# driver_module.net
KiCad netlist of a schematic drawn in EAGLE
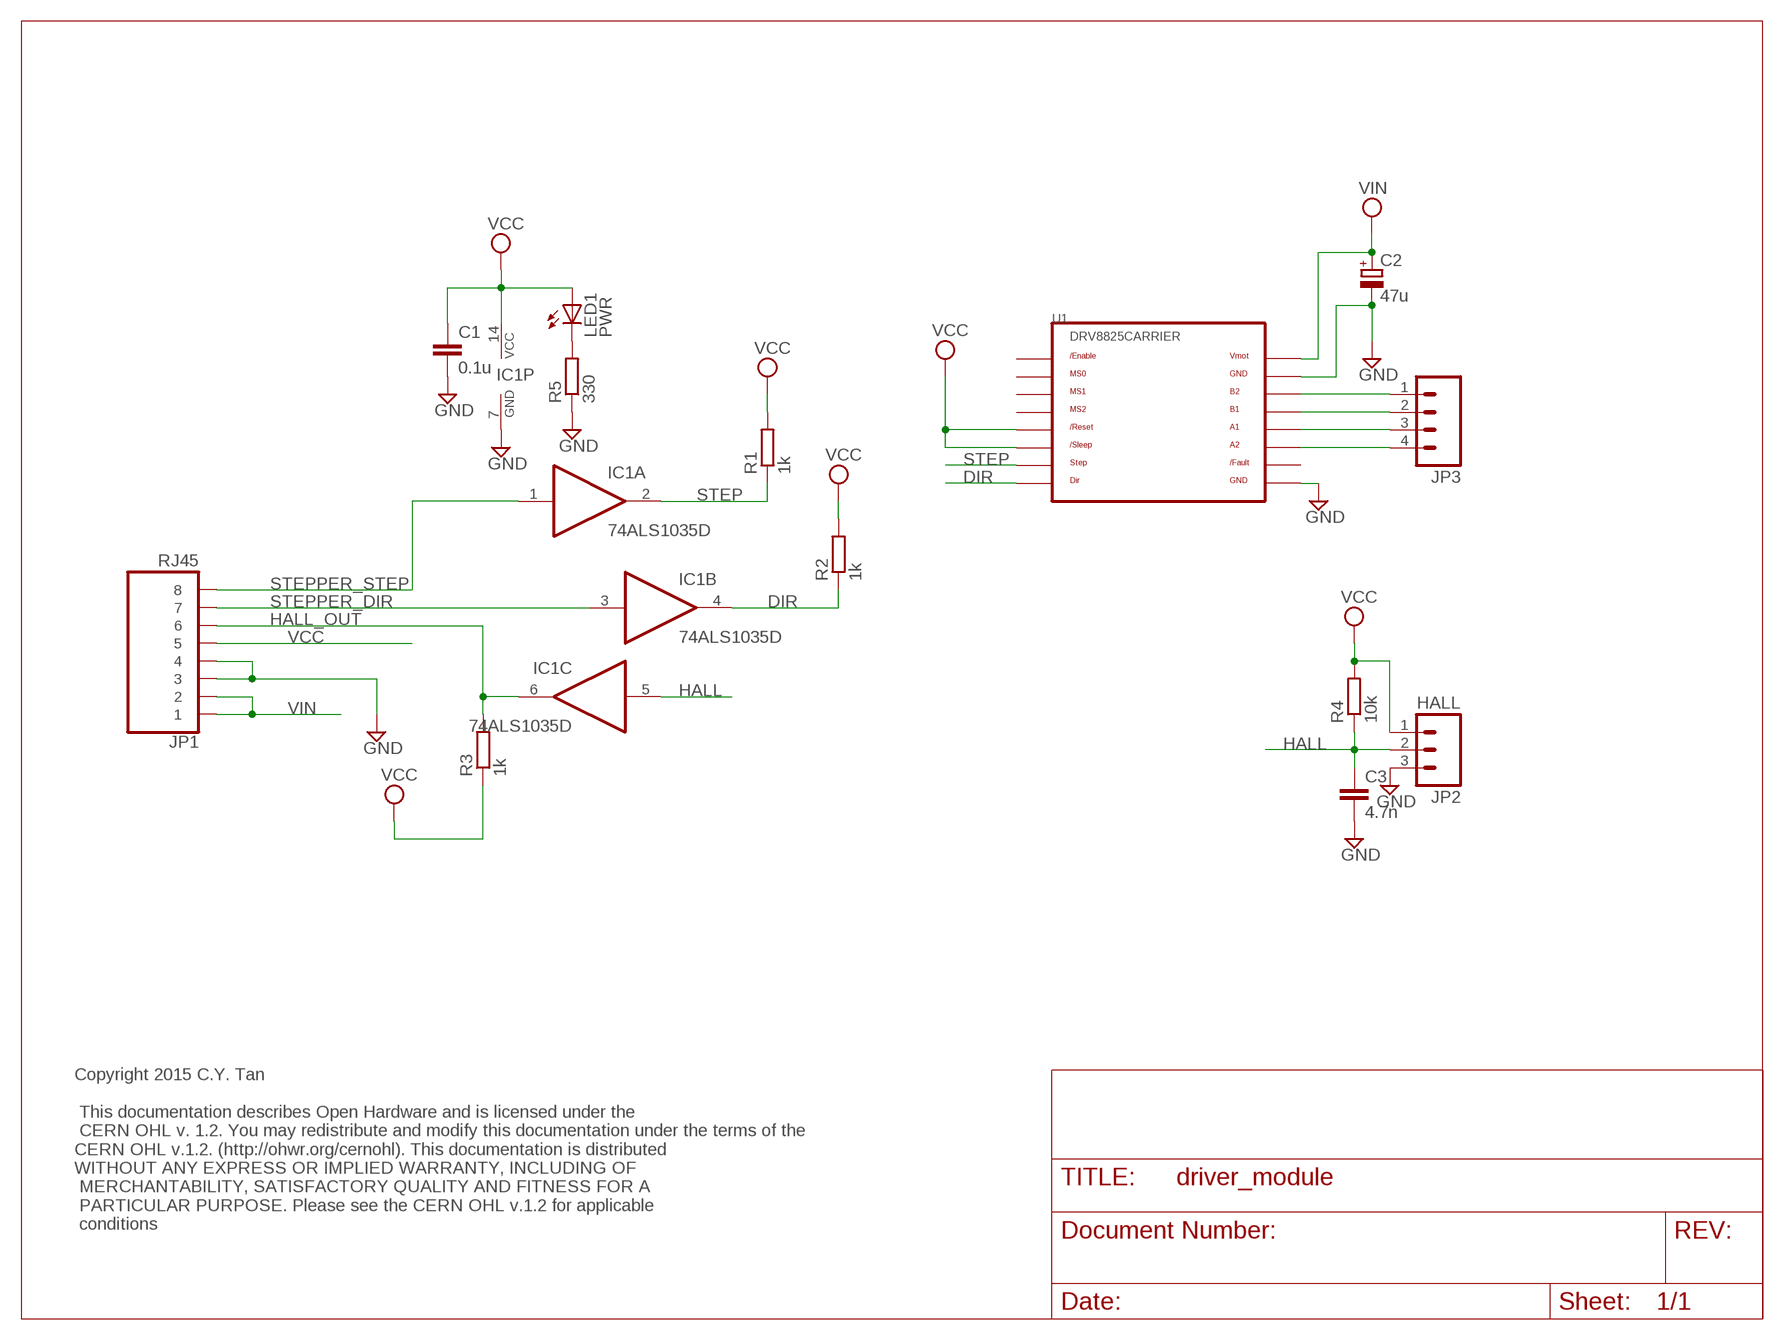
[diagram p0: schematic, sheet 1]

(export (version "E")
  (design (tool "Eeschema 10.0.6"))
  (components
    (comp (ref "C1")
      (value "0.1u")
      (footprint "eagle-import:C1206")
      (libsource (lib "eagle-import") (part "C-EUC1206"))
    )
    (comp (ref "C2")
      (value "47u")
      (footprint "eagle-import:E2,5-6")
      (libsource (lib "eagle-import") (part "CPOL-EUE2.5-6"))
    )
    (comp (ref "C3")
      (value "4.7n")
      (footprint "eagle-import:C1206")
      (libsource (lib "eagle-import") (part "C-EUC1206"))
    )
    (comp (ref "IC1")
      (value "74ALS1035D")
      (footprint "eagle-import:SO14")
      (libsource (lib "eagle-import") (part "74ALS1035D"))
    )
    (comp (ref "JP1")
      (value "RJ45")
      (footprint "eagle-import:RJ45-8")
      (libsource (lib "eagle-import") (part "RJ45-8PTH"))
    )
    (comp (ref "JP2")
      (value "HALL")
      (footprint "eagle-import:1X03")
      (libsource (lib "eagle-import") (part "M03PTH"))
    )
    (comp (ref "JP3")
      (value "M04PTH")
      (footprint "eagle-import:1X04")
      (libsource (lib "eagle-import") (part "M04PTH"))
    )
    (comp (ref "LED1")
      (value "PWR")
      (footprint "eagle-import:CHIPLED_1206")
      (libsource (lib "eagle-import") (part "LEDCHIPLED_1206"))
    )
    (comp (ref "R1")
      (value "1k")
      (footprint "eagle-import:M0805")
      (libsource (lib "eagle-import") (part "R-EU_M0805"))
    )
    (comp (ref "R2")
      (value "1k")
      (footprint "eagle-import:M0805")
      (libsource (lib "eagle-import") (part "R-EU_M0805"))
    )
    (comp (ref "R3")
      (value "1k")
      (footprint "eagle-import:M0805")
      (libsource (lib "eagle-import") (part "R-EU_M0805"))
    )
    (comp (ref "R4")
      (value "10k")
      (footprint "eagle-import:M0805")
      (libsource (lib "eagle-import") (part "R-EU_M0805"))
    )
    (comp (ref "R5")
      (value "330")
      (footprint "eagle-import:M0805")
      (libsource (lib "eagle-import") (part "R-EU_M0805"))
    )
    (comp (ref "U1")
      (value "DRV8825CARRIER")
      (footprint "eagle-import:DRV8825CARRIER")
      (libsource (lib "eagle-import") (part "DRV8825CARRIER"))
    )
  )
  (nets
    (net (code "1") (name "/DIR") (class "Default")
      (node (ref "IC1") (pin "4") (pinfunction "O_4") (pintype "open_collector"))
      (node (ref "R2") (pin "1") (pinfunction "1_1") (pintype "passive"))
      (node (ref "U1") (pin "DIR") (pinfunction "DIR_DIR") (pintype "input"))
    )
    (net (code "2") (name "/HALL") (class "Default")
      (node (ref "C3") (pin "1") (pinfunction "1_1") (pintype "passive"))
      (node (ref "IC1") (pin "5") (pinfunction "I_5") (pintype "input"))
      (node (ref "JP2") (pin "2") (pinfunction "2_2") (pintype "passive"))
      (node (ref "R4") (pin "1") (pinfunction "1_1") (pintype "passive"))
    )
    (net (code "3") (name "/HALL_OUT") (class "Default")
      (node (ref "IC1") (pin "6") (pinfunction "O_6") (pintype "open_collector"))
      (node (ref "JP1") (pin "6") (pinfunction "6_6") (pintype "bidirectional"))
      (node (ref "R3") (pin "2") (pinfunction "2_2") (pintype "passive"))
    )
    (net (code "4") (name "/STEP") (class "Default")
      (node (ref "IC1") (pin "2") (pinfunction "O_2") (pintype "open_collector"))
      (node (ref "R1") (pin "1") (pinfunction "1_1") (pintype "passive"))
      (node (ref "U1") (pin "STEP") (pinfunction "STEP_STEP") (pintype "input"))
    )
    (net (code "5") (name "/STEPPER_DIR") (class "Default")
      (node (ref "IC1") (pin "3") (pinfunction "I_3") (pintype "input"))
      (node (ref "JP1") (pin "7") (pinfunction "7_7") (pintype "bidirectional"))
    )
    (net (code "6") (name "/STEPPER_STEP") (class "Default")
      (node (ref "IC1") (pin "1") (pinfunction "I_1") (pintype "input"))
      (node (ref "JP1") (pin "8") (pinfunction "8_8") (pintype "bidirectional"))
    )
    (net (code "7") (name "/{slash}FAULT") (class "Default")
      (node (ref "U1") (pin "/FAULT") (pinfunction "/FAULT_/FAULT") (pintype "power_in"))
    )
    (net (code "8") (name "GND") (class "Default")
      (node (ref "C1") (pin "2") (pinfunction "2_2") (pintype "passive"))
      (node (ref "C2") (pin "-") (pinfunction "-_-") (pintype "passive"))
      (node (ref "C3") (pin "2") (pinfunction "2_2") (pintype "passive"))
      (node (ref "IC1") (pin "7") (pinfunction "GND_7") (pintype "power_in"))
      (node (ref "JP1") (pin "3") (pinfunction "3_3") (pintype "bidirectional"))
      (node (ref "JP1") (pin "4") (pinfunction "4_4") (pintype "bidirectional"))
      (node (ref "JP2") (pin "3") (pinfunction "3_3") (pintype "passive"))
      (node (ref "R5") (pin "1") (pinfunction "1_1") (pintype "passive"))
      (node (ref "U1") (pin "GND@0") (pinfunction "GND_GND@0") (pintype "power_in"))
      (node (ref "U1") (pin "GND@1") (pinfunction "GND_GND@1") (pintype "power_in"))
    )
    (net (code "9") (name "Net-(JP3-Pad1)") (class "Default")
      (node (ref "JP3") (pin "1") (pinfunction "1_1") (pintype "passive"))
      (node (ref "U1") (pin "B2") (pinfunction "B2_B2") (pintype "output"))
    )
    (net (code "10") (name "Net-(JP3-Pad2)") (class "Default")
      (node (ref "JP3") (pin "2") (pinfunction "2_2") (pintype "passive"))
      (node (ref "U1") (pin "B1") (pinfunction "B1_B1") (pintype "output"))
    )
    (net (code "11") (name "Net-(JP3-Pad3)") (class "Default")
      (node (ref "JP3") (pin "3") (pinfunction "3_3") (pintype "passive"))
      (node (ref "U1") (pin "A1") (pinfunction "A1_A1") (pintype "output"))
    )
    (net (code "12") (name "Net-(JP3-Pad4)") (class "Default")
      (node (ref "JP3") (pin "4") (pinfunction "4_4") (pintype "passive"))
      (node (ref "U1") (pin "A2") (pinfunction "A2_A2") (pintype "output"))
    )
    (net (code "13") (name "Net-(LED1-PadC)") (class "Default")
      (node (ref "LED1") (pin "C") (pinfunction "C_C") (pintype "passive"))
      (node (ref "R5") (pin "2") (pinfunction "2_2") (pintype "passive"))
    )
    (net (code "14") (name "VCC") (class "Default")
      (node (ref "C1") (pin "1") (pinfunction "1_1") (pintype "passive"))
      (node (ref "IC1") (pin "14") (pinfunction "VCC_14") (pintype "power_in"))
      (node (ref "JP1") (pin "5") (pinfunction "5_5") (pintype "bidirectional"))
      (node (ref "JP2") (pin "1") (pinfunction "1_1") (pintype "passive"))
      (node (ref "LED1") (pin "A") (pinfunction "A_A") (pintype "passive"))
      (node (ref "R1") (pin "2") (pinfunction "2_2") (pintype "passive"))
      (node (ref "R2") (pin "2") (pinfunction "2_2") (pintype "passive"))
      (node (ref "R3") (pin "1") (pinfunction "1_1") (pintype "passive"))
      (node (ref "R4") (pin "2") (pinfunction "2_2") (pintype "passive"))
      (node (ref "U1") (pin "/RESET") (pinfunction "/RESET_/RESET") (pintype "input"))
      (node (ref "U1") (pin "/SLEEP") (pinfunction "/SLEEP_/SLEEP") (pintype "input"))
    )
    (net (code "15") (name "VIN") (class "Default")
      (node (ref "C2") (pin "+") (pinfunction "+_+") (pintype "passive"))
      (node (ref "JP1") (pin "1") (pinfunction "1_1") (pintype "bidirectional"))
      (node (ref "JP1") (pin "2") (pinfunction "2_2") (pintype "bidirectional"))
      (node (ref "U1") (pin "VMOT") (pinfunction "VMOT_VMOT") (pintype "power_in"))
    )
    (net (code "16") (name "unconnected-(U1-MS0-PadM0)") (class "Default")
      (node (ref "U1") (pin "M0") (pinfunction "MS0_M0") (pintype "input"))
    )
    (net (code "17") (name "unconnected-(U1-MS1-PadM1)") (class "Default")
      (node (ref "U1") (pin "M1") (pinfunction "MS1_M1") (pintype "input"))
    )
    (net (code "18") (name "unconnected-(U1-MS2-PadM2)") (class "Default")
      (node (ref "U1") (pin "M2") (pinfunction "MS2_M2") (pintype "input"))
    )
    (net (code "19") (name "unconnected-(U1-Pad{slash}ENABLE)") (class "Default")
      (node (ref "U1") (pin "/ENABLE") (pinfunction "/ENABLE_/ENABLE") (pintype "input"))
    )
  )
)
